# BV100011_ControlConnector.net
KiCad netlist of a schematic drawn in Altium Designer
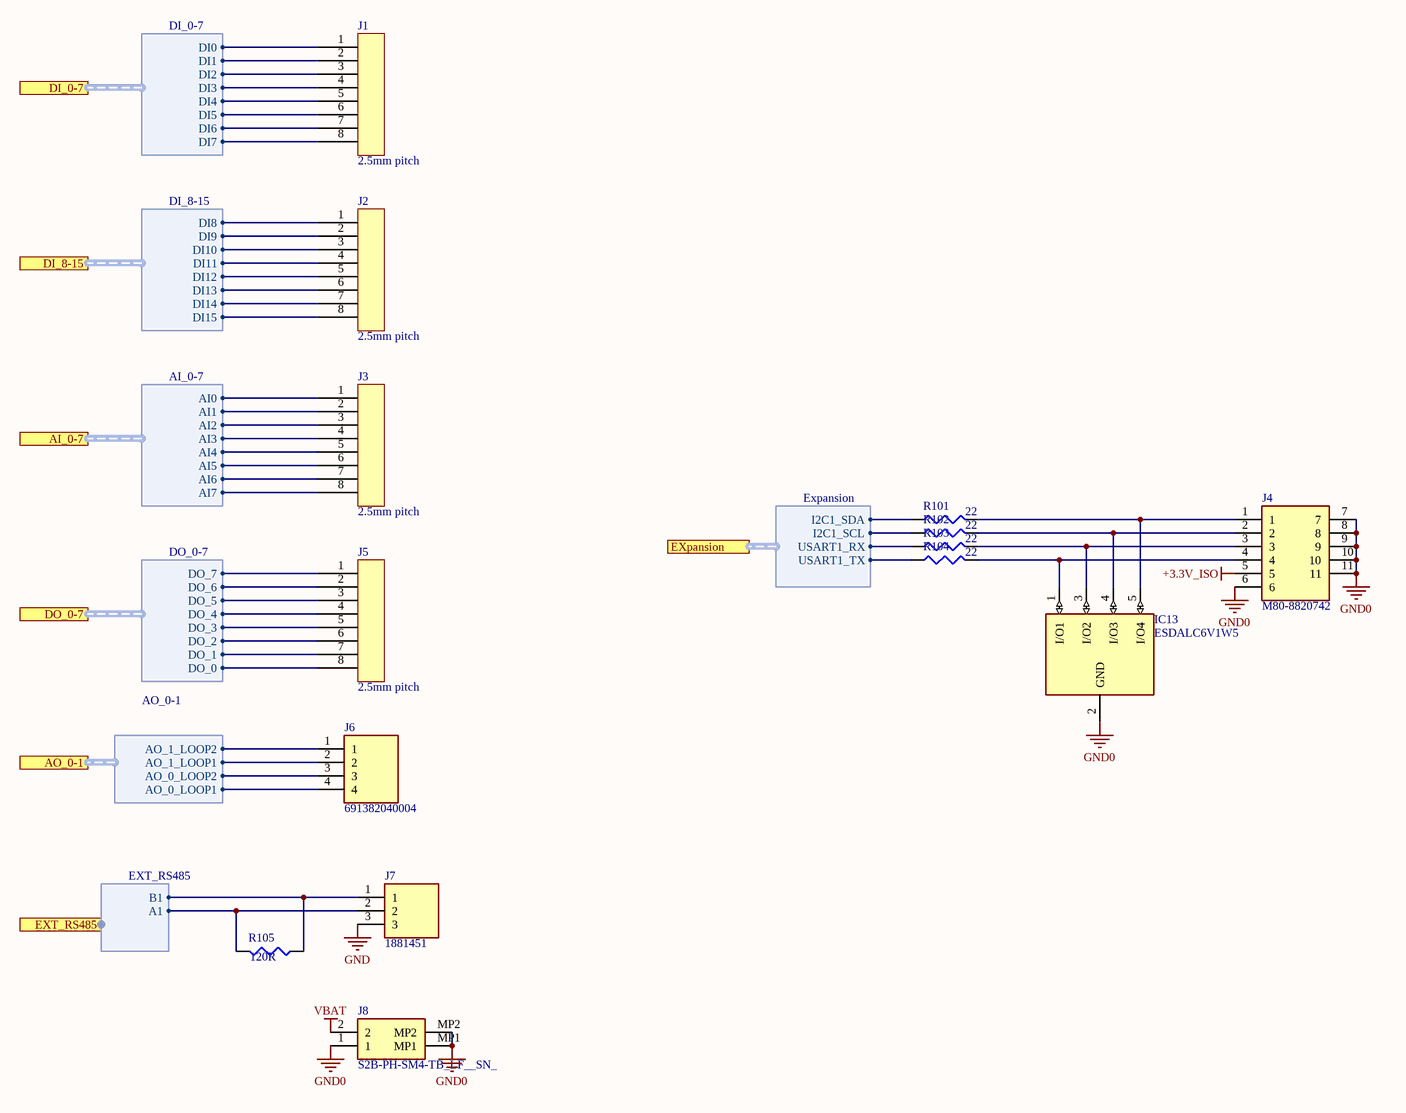
[diagram p0: BV100011_ControlConnector.SchDoc]

(export (version "E")
  (design (tool "Eeschema 10.0.6"))
  (components
    (comp (ref "IC13")
      (value "ESDALC6V1W5")
      (footprint "SOT65P210X110-5N")
      (description "Integrated Circuit")
      (fields
        (field (name "MOUSER PART NUMBER") "511-ESDALC6V1W5")
        (field (name "RS PART NUMBER") "0250044P")
      )
      (libsource (lib "SamacSys") (part "ESDALC6V1W5"))
    )
    (comp (ref "J1")
      (value "2.5mm pitch")
      (footprint "2.5mm pitch")
      (description "1881503")
      (libsource (lib "Headers 8 pin 2.5mm Pitch") (part "2.5mm pitch"))
    )
    (comp (ref "J2")
      (value "2.5mm pitch")
      (footprint "2.5mm pitch")
      (description "1881503")
      (libsource (lib "Headers 8 pin 2.5mm Pitch") (part "2.5mm pitch"))
    )
    (comp (ref "J3")
      (value "2.5mm pitch")
      (footprint "2.5mm pitch")
      (description "1881503")
      (libsource (lib "Headers 8 pin 2.5mm Pitch") (part "2.5mm pitch"))
    )
    (comp (ref "J4")
      (value "M80-8820742")
      (footprint "SamacSys:M80-8820742")
      (description "Connector")
      (fields (field (name "MOUSER PART NUMBER") "855-M80-8820742"))
      (libsource (lib "*") (part "M80-8820742"))
    )
    (comp (ref "J5")
      (value "2.5mm pitch")
      (footprint "2.5mm pitch")
      (description "1881503")
      (libsource (lib "Headers 8 pin 2.5mm Pitch") (part "2.5mm pitch"))
    )
    (comp (ref "J6")
      (value "691382040004")
      (footprint "SamacSys:SHDRRA4W80P0X250_1X4_2200X1010X810P")
      (description "Connector")
      (fields (field (name "MOUSER PART NUMBER") "710-691382040004"))
      (libsource (lib "*") (part "691382040004"))
    )
    (comp (ref "J7")
      (value "1881451")
      (footprint "SHDR3W100P0X250_1X3_940X1010X810P")
      (description "Connector")
      (fields (field (name "MOUSER PART NUMBER") "651-1881451") (field (name "RS PART NUMBER") "3579543"))
      (libsource (lib "1881451") (part "1881451"))
    )
    (comp (ref "J8")
      (value "S2B-PH-SM4-TB_LF__SN_")
      (footprint "SamacSys:S2BPHSM4TBLFSN")
      (description "Connector")
      (fields (field (name "MANUFACTURER_PART_NUMBER") "S2B-PH-SM4-TB(LF)(SN)"))
      (libsource (lib "*") (part "S2B-PH-SM4-TB_LF__SN_"))
    )
    (comp (ref "R101")
      (value "22")
      (footprint "J1-0603")
      (description "Resistor")
      (fields (field (name "PUBLISHER") "Altium Limited"))
      (libsource (lib "Miscellaneous Devices") (part "Res3"))
    )
    (comp (ref "R102")
      (value "22")
      (footprint "J1-0603")
      (description "Resistor")
      (fields (field (name "PUBLISHER") "Altium Limited"))
      (libsource (lib "Miscellaneous Devices") (part "Res3"))
    )
    (comp (ref "R103")
      (value "22")
      (footprint "J1-0603")
      (description "Resistor")
      (fields (field (name "PUBLISHER") "Altium Limited"))
      (libsource (lib "Miscellaneous Devices") (part "Res3"))
    )
    (comp (ref "R104")
      (value "22")
      (footprint "J1-0603")
      (description "Resistor")
      (fields (field (name "PUBLISHER") "Altium Limited"))
      (libsource (lib "Miscellaneous Devices") (part "Res3"))
    )
    (comp (ref "R105")
      (value "120R")
      (footprint "14-1210")
      (description "Resistor")
      (fields (field (name "PUBLISHER") "Altium Limited"))
      (libsource (lib "Miscellaneous Devices") (part "Res3"))
    )
  )
  (nets
    (net (code "8") (name "+3.3V_ISO") (class "Default")
      (node (ref "J4") (pin "5") (pinfunction "5_5") (pintype "passive"))
    )
    (net (code "9") (name "/A1") (class "Default")
      (node (ref "J7") (pin "2") (pinfunction "2_2") (pintype "passive"))
      (node (ref "R105") (pin "2") (pinfunction "2_2") (pintype "passive"))
    )
    (net (code "10") (name "/AI0") (class "Default")
      (node (ref "J3") (pin "1") (pinfunction "1_1") (pintype "passive"))
    )
    (net (code "11") (name "/AI1") (class "Default")
      (node (ref "J3") (pin "2") (pinfunction "2_2") (pintype "passive"))
    )
    (net (code "12") (name "/AI2") (class "Default")
      (node (ref "J3") (pin "3") (pinfunction "3_3") (pintype "passive"))
    )
    (net (code "13") (name "/AI3") (class "Default")
      (node (ref "J3") (pin "4") (pinfunction "4_4") (pintype "passive"))
    )
    (net (code "14") (name "/AI4") (class "Default")
      (node (ref "J3") (pin "5") (pinfunction "5_5") (pintype "passive"))
    )
    (net (code "15") (name "/AI5") (class "Default")
      (node (ref "J3") (pin "6") (pinfunction "6_6") (pintype "passive"))
    )
    (net (code "16") (name "/AI6") (class "Default")
      (node (ref "J3") (pin "7") (pinfunction "7_7") (pintype "passive"))
    )
    (net (code "17") (name "/AI7") (class "Default")
      (node (ref "J3") (pin "8") (pinfunction "8_8") (pintype "passive"))
    )
    (net (code "18") (name "/AO_0_LOOP1") (class "Default")
      (node (ref "J6") (pin "4") (pinfunction "4_4") (pintype "passive"))
    )
    (net (code "19") (name "/AO_0_LOOP2") (class "Default")
      (node (ref "J6") (pin "3") (pinfunction "3_3") (pintype "passive"))
    )
    (net (code "20") (name "/AO_1_LOOP1") (class "Default")
      (node (ref "J6") (pin "2") (pinfunction "2_2") (pintype "passive"))
    )
    (net (code "21") (name "/AO_1_LOOP2") (class "Default")
      (node (ref "J6") (pin "1") (pinfunction "1_1") (pintype "passive"))
    )
    (net (code "22") (name "/B1") (class "Default")
      (node (ref "J7") (pin "1") (pinfunction "1_1") (pintype "passive"))
      (node (ref "R105") (pin "1") (pinfunction "1_1") (pintype "passive"))
    )
    (net (code "23") (name "/DI0") (class "Default")
      (node (ref "J1") (pin "1") (pinfunction "1_1") (pintype "passive"))
    )
    (net (code "24") (name "/DI1") (class "Default")
      (node (ref "J1") (pin "2") (pinfunction "2_2") (pintype "passive"))
    )
    (net (code "25") (name "/DI2") (class "Default")
      (node (ref "J1") (pin "3") (pinfunction "3_3") (pintype "passive"))
    )
    (net (code "26") (name "/DI3") (class "Default")
      (node (ref "J1") (pin "4") (pinfunction "4_4") (pintype "passive"))
    )
    (net (code "27") (name "/DI4") (class "Default")
      (node (ref "J1") (pin "5") (pinfunction "5_5") (pintype "passive"))
    )
    (net (code "28") (name "/DI5") (class "Default")
      (node (ref "J1") (pin "6") (pinfunction "6_6") (pintype "passive"))
    )
    (net (code "29") (name "/DI6") (class "Default")
      (node (ref "J1") (pin "7") (pinfunction "7_7") (pintype "passive"))
    )
    (net (code "30") (name "/DI7") (class "Default")
      (node (ref "J1") (pin "8") (pinfunction "8_8") (pintype "passive"))
    )
    (net (code "31") (name "/DI8") (class "Default")
      (node (ref "J2") (pin "1") (pinfunction "1_1") (pintype "passive"))
    )
    (net (code "32") (name "/DI9") (class "Default")
      (node (ref "J2") (pin "2") (pinfunction "2_2") (pintype "passive"))
    )
    (net (code "33") (name "/DI10") (class "Default")
      (node (ref "J2") (pin "3") (pinfunction "3_3") (pintype "passive"))
    )
    (net (code "34") (name "/DI11") (class "Default")
      (node (ref "J2") (pin "4") (pinfunction "4_4") (pintype "passive"))
    )
    (net (code "35") (name "/DI12") (class "Default")
      (node (ref "J2") (pin "5") (pinfunction "5_5") (pintype "passive"))
    )
    (net (code "36") (name "/DI13") (class "Default")
      (node (ref "J2") (pin "6") (pinfunction "6_6") (pintype "passive"))
    )
    (net (code "37") (name "/DI14") (class "Default")
      (node (ref "J2") (pin "7") (pinfunction "7_7") (pintype "passive"))
    )
    (net (code "38") (name "/DI15") (class "Default")
      (node (ref "J2") (pin "8") (pinfunction "8_8") (pintype "passive"))
    )
    (net (code "39") (name "/DO_0") (class "Default")
      (node (ref "J5") (pin "8") (pinfunction "8_8") (pintype "passive"))
    )
    (net (code "40") (name "/DO_1") (class "Default")
      (node (ref "J5") (pin "7") (pinfunction "7_7") (pintype "passive"))
    )
    (net (code "41") (name "/DO_2") (class "Default")
      (node (ref "J5") (pin "6") (pinfunction "6_6") (pintype "passive"))
    )
    (net (code "42") (name "/DO_3") (class "Default")
      (node (ref "J5") (pin "5") (pinfunction "5_5") (pintype "passive"))
    )
    (net (code "43") (name "/DO_4") (class "Default")
      (node (ref "J5") (pin "4") (pinfunction "4_4") (pintype "passive"))
    )
    (net (code "44") (name "/DO_5") (class "Default")
      (node (ref "J5") (pin "3") (pinfunction "3_3") (pintype "passive"))
    )
    (net (code "45") (name "/DO_6") (class "Default")
      (node (ref "J5") (pin "2") (pinfunction "2_2") (pintype "passive"))
    )
    (net (code "46") (name "/DO_7") (class "Default")
      (node (ref "J5") (pin "1") (pinfunction "1_1") (pintype "passive"))
    )
    (net (code "47") (name "/I2C1_SCL") (class "Default")
      (node (ref "R102") (pin "1") (pinfunction "1_1") (pintype "passive"))
    )
    (net (code "48") (name "/I2C1_SDA") (class "Default")
      (node (ref "R101") (pin "1") (pinfunction "1_1") (pintype "passive"))
    )
    (net (code "49") (name "/USART1_RX") (class "Default")
      (node (ref "R103") (pin "1") (pinfunction "1_1") (pintype "passive"))
    )
    (net (code "50") (name "/USART1_TX") (class "Default")
      (node (ref "R104") (pin "1") (pinfunction "1_1") (pintype "passive"))
    )
    (net (code "58") (name "GND") (class "Default")
      (node (ref "J7") (pin "3") (pinfunction "3_3") (pintype "passive"))
    )
    (net (code "59") (name "GND0") (class "Default")
      (node (ref "IC13") (pin "2") (pinfunction "GND_2") (pintype "power_in"))
      (node (ref "J4") (pin "10") (pinfunction "10_10") (pintype "passive"))
      (node (ref "J4") (pin "11") (pinfunction "11_11") (pintype "passive"))
      (node (ref "J4") (pin "6") (pinfunction "6_6") (pintype "passive"))
      (node (ref "J4") (pin "7") (pinfunction "7_7") (pintype "passive"))
      (node (ref "J4") (pin "8") (pinfunction "8_8") (pintype "passive"))
      (node (ref "J4") (pin "9") (pinfunction "9_9") (pintype "passive"))
      (node (ref "J8") (pin "1") (pinfunction "1_1") (pintype "passive"))
      (node (ref "J8") (pin "MP1") (pinfunction "MP1_MP1") (pintype "passive"))
      (node (ref "J8") (pin "MP2") (pinfunction "MP2_MP2") (pintype "passive"))
    )
    (net (code "60") (name "Net-(IC13-I{slash}O1)") (class "Default")
      (node (ref "IC13") (pin "1") (pinfunction "I/O1_1") (pintype "bidirectional"))
      (node (ref "J4") (pin "4") (pinfunction "4_4") (pintype "passive"))
      (node (ref "R104") (pin "2") (pinfunction "2_2") (pintype "passive"))
    )
    (net (code "61") (name "Net-(IC13-I{slash}O2)") (class "Default")
      (node (ref "IC13") (pin "3") (pinfunction "I/O2_3") (pintype "bidirectional"))
      (node (ref "J4") (pin "3") (pinfunction "3_3") (pintype "passive"))
      (node (ref "R103") (pin "2") (pinfunction "2_2") (pintype "passive"))
    )
    (net (code "62") (name "Net-(IC13-I{slash}O3)") (class "Default")
      (node (ref "IC13") (pin "4") (pinfunction "I/O3_4") (pintype "bidirectional"))
      (node (ref "J4") (pin "2") (pinfunction "2_2") (pintype "passive"))
      (node (ref "R102") (pin "2") (pinfunction "2_2") (pintype "passive"))
    )
    (net (code "63") (name "Net-(IC13-I{slash}O4)") (class "Default")
      (node (ref "IC13") (pin "5") (pinfunction "I/O4_5") (pintype "bidirectional"))
      (node (ref "J4") (pin "1") (pinfunction "1_1") (pintype "passive"))
      (node (ref "R101") (pin "2") (pinfunction "2_2") (pintype "passive"))
    )
    (net (code "64") (name "VBAT") (class "Default")
      (node (ref "J8") (pin "2") (pinfunction "2_2") (pintype "passive"))
    )
  )
)
